# power.net
KiCad netlist of a schematic drawn in Altium Designer
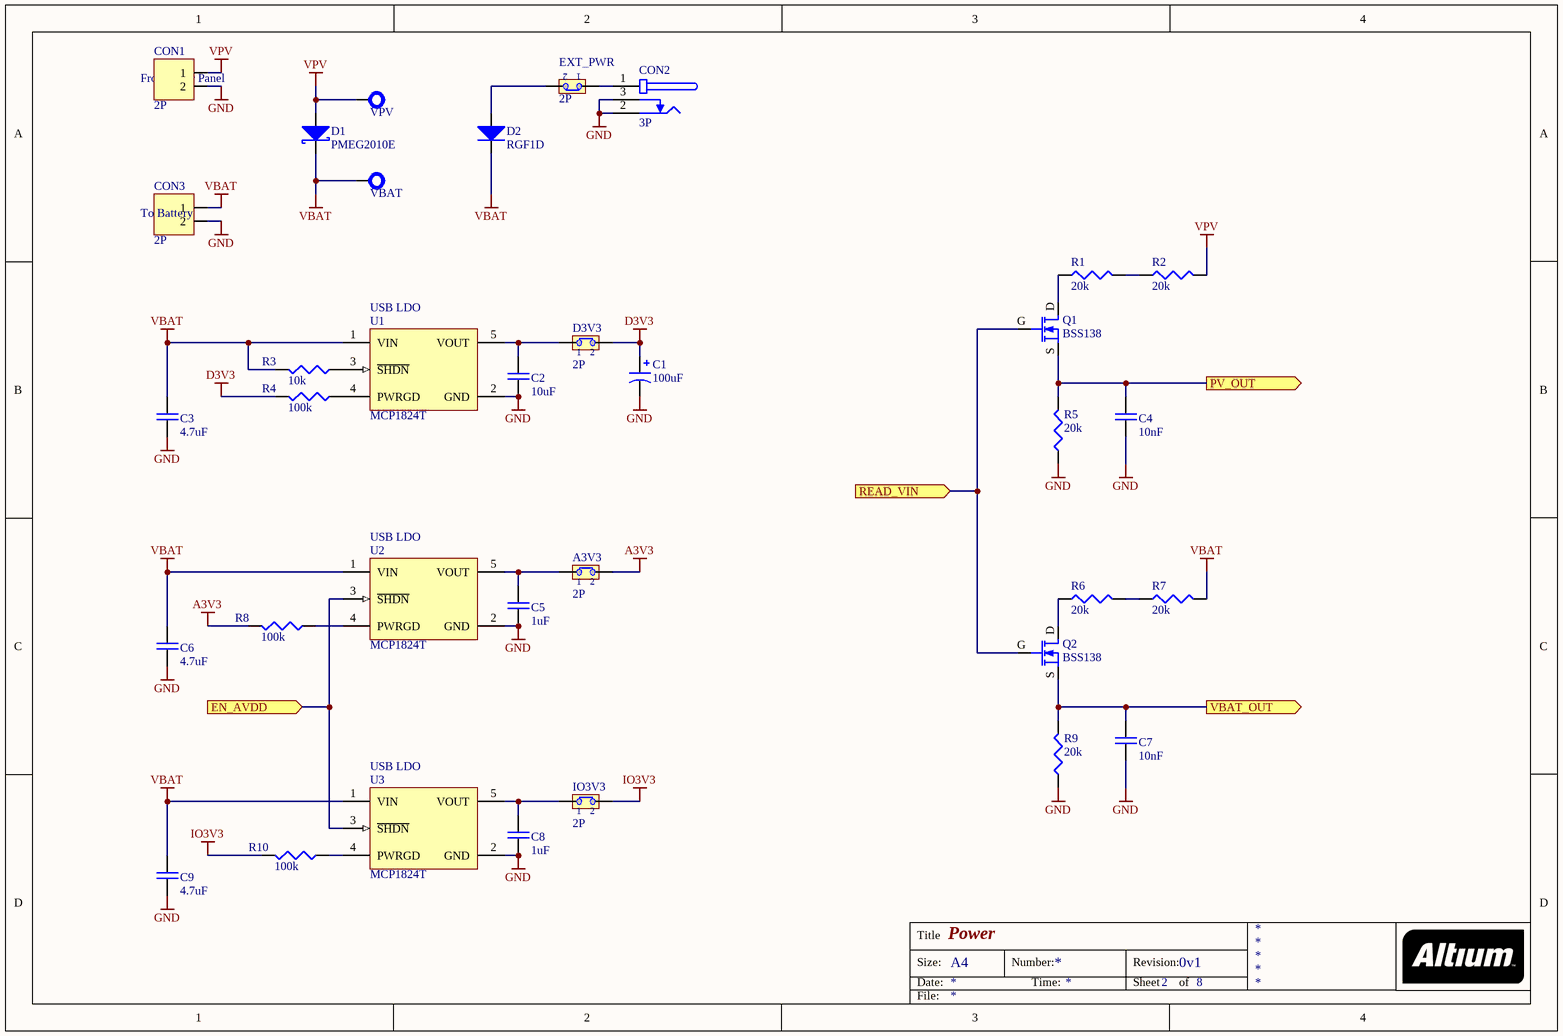
[diagram p0: power.SchDoc]

(export (version "E")
  (design (tool "Eeschema 10.0.6"))
  (components
    (comp (ref "A3V3")
      (value "2P")
      (footprint "SIP-2")
      (description "2-pin Jumper")
      (fields (field (name "OWNER") "Nuno Brum"))
      (libsource (lib "") (part "JMP2_1"))
    )
    (comp (ref "C1")
      (value "100uF")
      (footprint "RADIAL-2.5MM")
      (description "Polarized Capacitor")
      (fields (field (name "OWNER") "Nuno Brum"))
      (libsource (lib "Alcetronics_Devices") (part "CAP POL"))
    )
    (comp (ref "C2")
      (value "10uF")
      (footprint "0805")
      (description "Capacitor")
      (fields (field (name "OWNER") "Nuno Brum"))
      (libsource (lib "Alcetronics_Devices") (part "CAP"))
    )
    (comp (ref "C3")
      (value "4.7uF")
      (footprint "0805")
      (description "Capacitor")
      (fields (field (name "OWNER") "Nuno Brum"))
      (libsource (lib "Alcetronics_Devices") (part "CAP"))
    )
    (comp (ref "C4")
      (value "10nF")
      (footprint "0603")
      (description "Capacitor")
      (fields (field (name "OWNER") "Nuno Brum"))
      (libsource (lib "Alcetronics_Devices") (part "CAP"))
    )
    (comp (ref "C5")
      (value "1uF")
      (footprint "0805")
      (description "Capacitor")
      (fields (field (name "OWNER") "Nuno Brum"))
      (libsource (lib "Alcetronics_Devices") (part "CAP"))
    )
    (comp (ref "C6")
      (value "4.7uF")
      (footprint "0805")
      (description "Capacitor")
      (fields (field (name "OWNER") "Nuno Brum"))
      (libsource (lib "Alcetronics_Devices") (part "CAP"))
    )
    (comp (ref "C7")
      (value "10nF")
      (footprint "0603")
      (description "Capacitor")
      (fields (field (name "OWNER") "Nuno Brum"))
      (libsource (lib "Alcetronics_Devices") (part "CAP"))
    )
    (comp (ref "C8")
      (value "1uF")
      (footprint "0805")
      (description "Capacitor")
      (fields (field (name "OWNER") "Nuno Brum"))
      (libsource (lib "Alcetronics_Devices") (part "CAP"))
    )
    (comp (ref "C9")
      (value "4.7uF")
      (footprint "0805")
      (description "Capacitor")
      (fields (field (name "OWNER") "Nuno Brum"))
      (libsource (lib "Alcetronics_Devices") (part "CAP"))
    )
    (comp (ref "CON1")
      (value "2P")
      (footprint "JST-2MM")
      (description "Connector 2 pins")
      (fields (field (name "OWNER") "Rui Rebelo"))
      (libsource (lib "Alcetronics_EM") (part "CON02"))
    )
    (comp (ref "CON2")
      (value "3P")
      (footprint "JACKPOW/PD-2.5MM-TH")
      (description "Jack Power with insertion detect")
      (fields (field (name "OWNER") "Gonçalo Costa"))
      (libsource (lib "Alcetronics_EM") (part "JACK POWER PD"))
    )
    (comp (ref "CON3")
      (value "2P")
      (footprint "INTERLOCK2-5MM")
      (description "Connector 2 pins")
      (fields (field (name "OWNER") "Rui Rebelo"))
      (libsource (lib "Alcetronics_EM") (part "CON02"))
    )
    (comp (ref "D1")
      (value "PMEG2010E")
      (footprint "SOD-123")
      (description "Small Signal Schottky Diode")
      (fields (field (name "OWNER") "Nuno Brum"))
      (libsource (lib "Alcetronics_Devices") (part "Diode Schottky"))
    )
    (comp (ref "D2")
      (value "RGF1D")
      (footprint "DO-214BA")
      (description "Vishay Standard Avalanche Sinterglass Diode")
      (fields (field (name "OWNER") "Nuno Brum"))
      (libsource (lib "Alcetronics_Devices") (part "Diode"))
    )
    (comp (ref "D3V3")
      (value "2P")
      (footprint "SIP-2")
      (description "2-pin Jumper")
      (fields (field (name "OWNER") "Nuno Brum"))
      (libsource (lib "") (part "JMP2_1"))
    )
    (comp (ref "EXT_PWR")
      (value "2P")
      (footprint "SIP-2")
      (description "2-pin Jumper")
      (fields (field (name "OWNER") "Nuno Brum"))
      (libsource (lib "Alcetronics_EM") (part "JMP2"))
    )
    (comp (ref "IO3V3")
      (value "2P")
      (footprint "SIP-2")
      (description "2-pin Jumper")
      (fields (field (name "OWNER") "Nuno Brum"))
      (libsource (lib "") (part "JMP2_1"))
    )
    (comp (ref "Q1")
      (value "BSS138")
      (footprint "SOT-23@GSD")
      (description "N-Channel Logic Level Enhancement Mode Field Effect Transistor")
      (fields (field (name "OWNER") "Nuno Brum"))
      (libsource (lib "Alcetronics_Devices") (part "MOSFET-N"))
    )
    (comp (ref "Q2")
      (value "BSS138")
      (footprint "SOT-23@GSD")
      (description "N-Channel Logic Level Enhancement Mode Field Effect Transistor")
      (fields (field (name "OWNER") "Nuno Brum"))
      (libsource (lib "Alcetronics_Devices") (part "MOSFET-N"))
    )
    (comp (ref "R1")
      (value "20k")
      (footprint "0603")
      (description "Resistor")
      (fields (field (name "OWNER") "Nuno Brum"))
      (libsource (lib "Alcetronics_Devices") (part "RES"))
    )
    (comp (ref "R2")
      (value "20k")
      (footprint "0603")
      (description "Resistor")
      (fields (field (name "OWNER") "Nuno Brum"))
      (libsource (lib "Alcetronics_Devices") (part "RES"))
    )
    (comp (ref "R3")
      (value "10k")
      (footprint "0603")
      (description "Resistor")
      (fields (field (name "OWNER") "Nuno Brum"))
      (libsource (lib "Alcetronics_Devices") (part "RES"))
    )
    (comp (ref "R4")
      (value "100k")
      (footprint "0603")
      (description "Resistor")
      (fields (field (name "OWNER") "Nuno Brum"))
      (libsource (lib "Alcetronics_Devices") (part "RES"))
    )
    (comp (ref "R5")
      (value "20k")
      (footprint "0603")
      (description "Resistor")
      (fields (field (name "OWNER") "Nuno Brum"))
      (libsource (lib "Alcetronics_Devices") (part "RES"))
    )
    (comp (ref "R6")
      (value "20k")
      (footprint "0603")
      (description "Resistor")
      (fields (field (name "OWNER") "Nuno Brum"))
      (libsource (lib "Alcetronics_Devices") (part "RES"))
    )
    (comp (ref "R7")
      (value "20k")
      (footprint "0603")
      (description "Resistor")
      (fields (field (name "OWNER") "Nuno Brum"))
      (libsource (lib "Alcetronics_Devices") (part "RES"))
    )
    (comp (ref "R8")
      (value "100k")
      (footprint "0603")
      (description "Resistor")
      (fields (field (name "OWNER") "Nuno Brum"))
      (libsource (lib "Alcetronics_Devices") (part "RES"))
    )
    (comp (ref "R9")
      (value "20k")
      (footprint "0603")
      (description "Resistor")
      (fields (field (name "OWNER") "Nuno Brum"))
      (libsource (lib "Alcetronics_Devices") (part "RES"))
    )
    (comp (ref "R10")
      (value "100k")
      (footprint "0603")
      (description "Resistor")
      (fields (field (name "OWNER") "Nuno Brum"))
      (libsource (lib "Alcetronics_Devices") (part "RES"))
    )
    (comp (ref "U1")
      (value "MCP1824T")
      (footprint "SOT-23-5")
      (fields (field (name "PUBLISHER") "Altium Limited"))
      (libsource (lib "Alcetronics_IC") (part "MCP1824T"))
    )
    (comp (ref "U2")
      (value "MCP1824T")
      (footprint "SOT-23-5")
      (fields (field (name "PUBLISHER") "Altium Limited"))
      (libsource (lib "Alcetronics_IC") (part "MCP1824T"))
    )
    (comp (ref "U3")
      (value "MCP1824T")
      (footprint "SOT-23-5")
      (fields (field (name "PUBLISHER") "Altium Limited"))
      (libsource (lib "Alcetronics_IC") (part "MCP1824T"))
    )
    (comp (ref "VBAT")
      (value "Test Point")
      (footprint "TERMINAL")
      (description "Test/Probe Point")
      (fields (field (name "OWNER") "Nuno Brum"))
      (libsource (lib "Alcetronics_EM") (part "TEST-PROBE"))
    )
    (comp (ref "VPV")
      (value "Test Point")
      (footprint "TERMINAL")
      (description "Test/Probe Point")
      (fields (field (name "OWNER") "Nuno Brum"))
      (libsource (lib "Alcetronics_EM") (part "TEST-PROBE"))
    )
  )
  (nets
    (net (code "1") (name "/EN_AVDD") (class "Default")
      (node (ref "U2") (pin "3") (pinfunction "~{SHDN}_3") (pintype "input"))
      (node (ref "U3") (pin "3") (pinfunction "~{SHDN}_3") (pintype "input"))
    )
    (net (code "2") (name "/PV_OUT") (class "Default")
      (node (ref "C4") (pin "2") (pinfunction "2_2") (pintype "passive"))
      (node (ref "Q1") (pin "S") (pinfunction "S_S") (pintype "passive"))
      (node (ref "R5") (pin "2") (pinfunction "2_2") (pintype "passive"))
    )
    (net (code "3") (name "/READ_VIN") (class "Default")
      (node (ref "Q1") (pin "G") (pinfunction "G_G") (pintype "passive"))
      (node (ref "Q2") (pin "G") (pinfunction "G_G") (pintype "passive"))
    )
    (net (code "4") (name "/VBAT_OUT") (class "Default")
      (node (ref "C7") (pin "2") (pinfunction "2_2") (pintype "passive"))
      (node (ref "Q2") (pin "S") (pinfunction "S_S") (pintype "passive"))
      (node (ref "R9") (pin "2") (pinfunction "2_2") (pintype "passive"))
    )
    (net (code "5") (name "A3V3") (class "Default")
      (node (ref "A3V3") (pin "2") (pinfunction "2_2") (pintype "passive"))
      (node (ref "R8") (pin "2") (pinfunction "2_2") (pintype "passive"))
    )
    (net (code "6") (name "D3V3") (class "Default")
      (node (ref "C1") (pin "1") (pinfunction "P_1") (pintype "passive"))
      (node (ref "D3V3") (pin "2") (pinfunction "2_2") (pintype "passive"))
      (node (ref "R4") (pin "2") (pinfunction "2_2") (pintype "passive"))
    )
    (net (code "7") (name "GND") (class "Default")
      (node (ref "C1") (pin "2") (pinfunction "N_2") (pintype "passive"))
      (node (ref "C2") (pin "1") (pinfunction "1_1") (pintype "passive"))
      (node (ref "C3") (pin "1") (pinfunction "1_1") (pintype "passive"))
      (node (ref "C4") (pin "1") (pinfunction "1_1") (pintype "passive"))
      (node (ref "C5") (pin "1") (pinfunction "1_1") (pintype "passive"))
      (node (ref "C6") (pin "1") (pinfunction "1_1") (pintype "passive"))
      (node (ref "C7") (pin "1") (pinfunction "1_1") (pintype "passive"))
      (node (ref "C8") (pin "1") (pinfunction "1_1") (pintype "passive"))
      (node (ref "C9") (pin "1") (pinfunction "1_1") (pintype "passive"))
      (node (ref "CON1") (pin "2") (pinfunction "2_2") (pintype "passive"))
      (node (ref "CON2") (pin "2") (pinfunction "2_2") (pintype "passive"))
      (node (ref "CON2") (pin "3") (pinfunction "3_3") (pintype "passive"))
      (node (ref "CON3") (pin "2") (pinfunction "2_2") (pintype "passive"))
      (node (ref "R5") (pin "1") (pinfunction "1_1") (pintype "passive"))
      (node (ref "R9") (pin "1") (pinfunction "1_1") (pintype "passive"))
      (node (ref "U1") (pin "2") (pinfunction "GND_2") (pintype "power_in"))
      (node (ref "U2") (pin "2") (pinfunction "GND_2") (pintype "power_in"))
      (node (ref "U3") (pin "2") (pinfunction "GND_2") (pintype "power_in"))
    )
    (net (code "8") (name "IO3V3") (class "Default")
      (node (ref "IO3V3") (pin "2") (pinfunction "2_2") (pintype "passive"))
      (node (ref "R10") (pin "2") (pinfunction "2_2") (pintype "passive"))
    )
    (net (code "9") (name "Net-(CON2-Pad1)") (class "Default")
      (node (ref "CON2") (pin "1") (pinfunction "1_1") (pintype "passive"))
      (node (ref "EXT_PWR") (pin "1") (pinfunction "1_1") (pintype "passive"))
    )
    (net (code "10") (name "Net-(D2-PadA)") (class "Default")
      (node (ref "D2") (pin "A") (pinfunction "A_A") (pintype "passive"))
      (node (ref "EXT_PWR") (pin "2") (pinfunction "2_2") (pintype "passive"))
    )
    (net (code "11") (name "Net-(Q1-PadD)") (class "Default")
      (node (ref "Q1") (pin "D") (pinfunction "D_D") (pintype "passive"))
      (node (ref "R1") (pin "1") (pinfunction "1_1") (pintype "passive"))
    )
    (net (code "12") (name "Net-(Q2-PadD)") (class "Default")
      (node (ref "Q2") (pin "D") (pinfunction "D_D") (pintype "passive"))
      (node (ref "R6") (pin "1") (pinfunction "1_1") (pintype "passive"))
    )
    (net (code "13") (name "Net-(R1-Pad2)") (class "Default")
      (node (ref "R1") (pin "2") (pinfunction "2_2") (pintype "passive"))
      (node (ref "R2") (pin "1") (pinfunction "1_1") (pintype "passive"))
    )
    (net (code "14") (name "Net-(R6-Pad2)") (class "Default")
      (node (ref "R6") (pin "2") (pinfunction "2_2") (pintype "passive"))
      (node (ref "R7") (pin "1") (pinfunction "1_1") (pintype "passive"))
    )
    (net (code "15") (name "Net-(U1-PWRGD)") (class "Default")
      (node (ref "R4") (pin "1") (pinfunction "1_1") (pintype "passive"))
      (node (ref "U1") (pin "4") (pinfunction "PWRGD_4") (pintype "power_in"))
    )
    (net (code "16") (name "Net-(U1-VOUT)") (class "Default")
      (node (ref "C2") (pin "2") (pinfunction "2_2") (pintype "passive"))
      (node (ref "D3V3") (pin "1") (pinfunction "1_1") (pintype "passive"))
      (node (ref "U1") (pin "5") (pinfunction "VOUT_5") (pintype "power_in"))
    )
    (net (code "17") (name "Net-(U1-~{SHDN})") (class "Default")
      (node (ref "R3") (pin "1") (pinfunction "1_1") (pintype "passive"))
      (node (ref "U1") (pin "3") (pinfunction "~{SHDN}_3") (pintype "input"))
    )
    (net (code "18") (name "Net-(U2-PWRGD)") (class "Default")
      (node (ref "R8") (pin "1") (pinfunction "1_1") (pintype "passive"))
      (node (ref "U2") (pin "4") (pinfunction "PWRGD_4") (pintype "power_in"))
    )
    (net (code "19") (name "Net-(U2-VOUT)") (class "Default")
      (node (ref "A3V3") (pin "1") (pinfunction "1_1") (pintype "passive"))
      (node (ref "C5") (pin "2") (pinfunction "2_2") (pintype "passive"))
      (node (ref "U2") (pin "5") (pinfunction "VOUT_5") (pintype "power_in"))
    )
    (net (code "20") (name "Net-(U3-PWRGD)") (class "Default")
      (node (ref "R10") (pin "1") (pinfunction "1_1") (pintype "passive"))
      (node (ref "U3") (pin "4") (pinfunction "PWRGD_4") (pintype "power_in"))
    )
    (net (code "21") (name "Net-(U3-VOUT)") (class "Default")
      (node (ref "C8") (pin "2") (pinfunction "2_2") (pintype "passive"))
      (node (ref "IO3V3") (pin "1") (pinfunction "1_1") (pintype "passive"))
      (node (ref "U3") (pin "5") (pinfunction "VOUT_5") (pintype "power_in"))
    )
    (net (code "22") (name "VBAT") (class "Default")
      (node (ref "C3") (pin "2") (pinfunction "2_2") (pintype "passive"))
      (node (ref "C6") (pin "2") (pinfunction "2_2") (pintype "passive"))
      (node (ref "C9") (pin "2") (pinfunction "2_2") (pintype "passive"))
      (node (ref "CON3") (pin "1") (pinfunction "1_1") (pintype "passive"))
      (node (ref "D1") (pin "K") (pinfunction "K_K") (pintype "passive"))
      (node (ref "D2") (pin "K") (pinfunction "K_K") (pintype "passive"))
      (node (ref "R3") (pin "2") (pinfunction "2_2") (pintype "passive"))
      (node (ref "R7") (pin "2") (pinfunction "2_2") (pintype "passive"))
      (node (ref "U1") (pin "1") (pinfunction "VIN_1") (pintype "power_in"))
      (node (ref "U2") (pin "1") (pinfunction "VIN_1") (pintype "power_in"))
      (node (ref "U3") (pin "1") (pinfunction "VIN_1") (pintype "power_in"))
      (node (ref "VBAT") (pin "1") (pinfunction "TP_1") (pintype "passive"))
    )
    (net (code "23") (name "VPV") (class "Default")
      (node (ref "CON1") (pin "1") (pinfunction "1_1") (pintype "passive"))
      (node (ref "D1") (pin "A") (pinfunction "A_A") (pintype "passive"))
      (node (ref "R2") (pin "2") (pinfunction "2_2") (pintype "passive"))
      (node (ref "VPV") (pin "1") (pinfunction "TP_1") (pintype "passive"))
    )
  )
)
